# PowerSupplies.net
KiCad netlist of a schematic drawn in Altium Designer
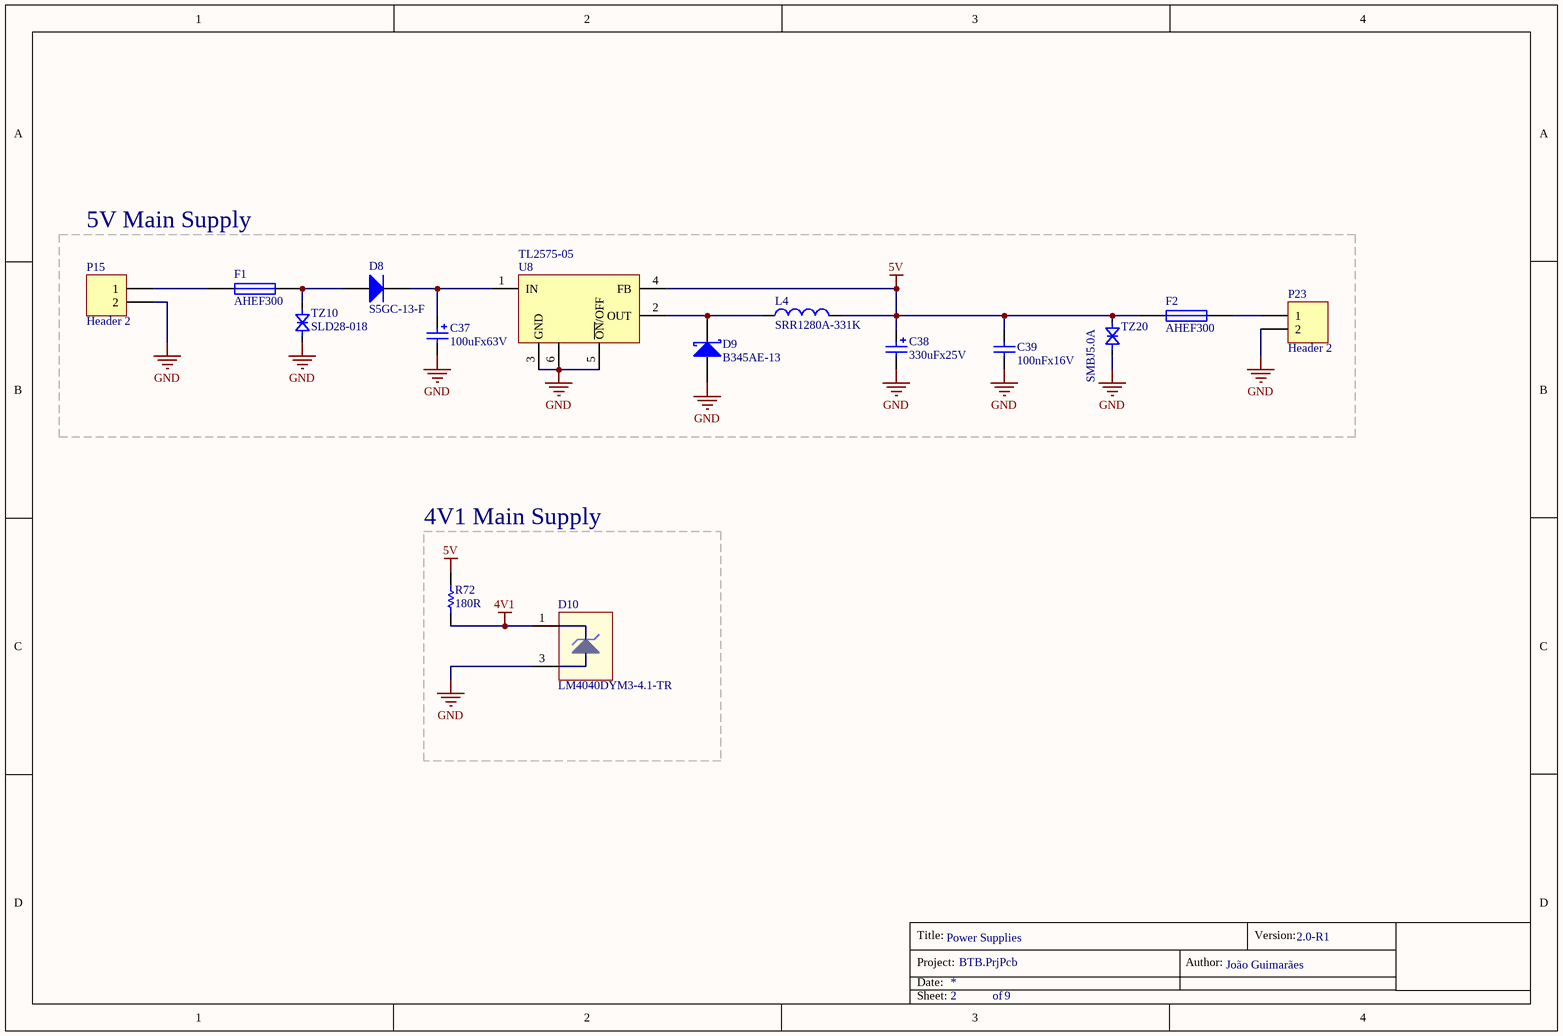
[diagram p0: PowerSupplies.SchDoc]

(export (version "E")
  (design (tool "Eeschema 10.0.6"))
  (components
    (comp (ref "C37")
      (value "100uFx63V")
      (footprint "DISC-CAP-ALU-G")
      (description "Polarized Capacitor (Surface Mount)")
      (libsource (lib "IntLib") (part "Cap Pol"))
    )
    (comp (ref "C38")
      (value "330uFx25V")
      (footprint "DISC-CAP-ALU-F")
      (description "Polarized Capacitor (Surface Mount)")
      (libsource (lib "IntLib") (part "Cap Pol"))
    )
    (comp (ref "C39")
      (value "100nFx16V")
      (footprint "DISC-0805")
      (description "Capacitor")
      (libsource (lib "IntLib") (part "Cap"))
    )
    (comp (ref "D8")
      (value "S5GC-13-F")
      (footprint "DISC-DO214-AB")
      (description "Default Diode")
      (fields (field (name "PUBLISHER") "Altium Limited"))
      (libsource (lib "IntLib") (part "Diode"))
    )
    (comp (ref "D9")
      (value "B345AE-13")
      (footprint "DISC-DO214-AC")
      (description "Schottky Diode")
      (fields (field (name "PUBLISHER") "Altium Limited"))
      (libsource (lib "IntLib") (part "D Schottky"))
    )
    (comp (ref "D10")
      (value "LM4040DYM3-4.1-TR")
      (footprint "DISC-SOT-23")
      (description "Shunt Voltage References")
      (libsource (lib "IntLib") (part "LM4040"))
    )
    (comp (ref "F1")
      (value "AHEF300")
      (footprint "DISC-PTC-0.2X0.4")
      (description "Fuse")
      (fields (field (name "PUBLISHER") "Altium Limited"))
      (libsource (lib "IntLib") (part "Fuse 1"))
    )
    (comp (ref "F2")
      (value "AHEF300")
      (footprint "DISC-PTC-0.2X0.4")
      (description "Fuse")
      (fields (field (name "PUBLISHER") "Altium Limited"))
      (libsource (lib "IntLib") (part "Fuse 1"))
    )
    (comp (ref "L4")
      (value "SRR1280A-331K")
      (footprint "DISC-IND-5050")
      (description "Chip Inductor")
      (libsource (lib "IntLib") (part "Inductor"))
    )
    (comp (ref "P15")
      (value "Header 2")
      (footprint "CON-FLEXWIRE-1.5MM2-1X2")
      (description "Header, 2-Pin")
      (fields (field (name "PUBLISHER") "Altium Limited"))
      (libsource (lib "IntLib") (part "Header 2"))
    )
    (comp (ref "P23")
      (value "Header 2")
      (footprint "CON-FLEXWIRE-1.5MM2-1X2")
      (description "Header, 2-Pin")
      (fields (field (name "PUBLISHER") "Altium Limited"))
      (libsource (lib "") (part "Header 2_1"))
    )
    (comp (ref "R72")
      (value "180R")
      (footprint "DISC-0805")
      (description "Resistor")
      (libsource (lib "IntLib") (part "Res"))
    )
    (comp (ref "TZ10")
      (value "SLD28-018")
      (footprint "DISC-DIODE-0.9-V")
      (description "TVZ-Bi-Directional")
      (libsource (lib "IntLib") (part "TVZ-Bi-Directional"))
    )
    (comp (ref "TZ20")
      (value "SMBJ5.0A")
      (footprint "DISC-DO214-AA")
      (description "TVZ-Bi-Directional")
      (libsource (lib "IntLib") (part "TVZ-Bi-Directional"))
    )
    (comp (ref "U8")
      (value "TL2575-05")
      (footprint "CI-TO-263")
      (description "Switching Voltage Regulators 1-A Step-Down Voltage")
      (libsource (lib "IntLib") (part "TL2575-05IKTTR"))
    )
  )
  (nets
    (net (code "1") (name "4V1") (class "Default")
      (node (ref "D10") (pin "1") (pinfunction "A_1") (pintype "passive"))
      (node (ref "R72") (pin "1") (pinfunction "1_1") (pintype "passive"))
    )
    (net (code "2") (name "5V") (class "Default")
      (node (ref "C38") (pin "1") (pinfunction "1_1") (pintype "passive"))
      (node (ref "C39") (pin "2") (pinfunction "2_2") (pintype "passive"))
      (node (ref "F2") (pin "1") (pinfunction "1_1") (pintype "passive"))
      (node (ref "L4") (pin "2") (pinfunction "2_2") (pintype "passive"))
      (node (ref "R72") (pin "2") (pinfunction "2_2") (pintype "passive"))
      (node (ref "TZ20") (pin "2") (pinfunction "K_2") (pintype "passive"))
      (node (ref "U8") (pin "4") (pinfunction "FB_4") (pintype "passive"))
    )
    (net (code "3") (name "GND") (class "Default")
      (node (ref "C37") (pin "2") (pinfunction "2_2") (pintype "passive"))
      (node (ref "C38") (pin "2") (pinfunction "2_2") (pintype "passive"))
      (node (ref "C39") (pin "1") (pinfunction "1_1") (pintype "passive"))
      (node (ref "D10") (pin "3") (pinfunction "K_3") (pintype "passive"))
      (node (ref "D9") (pin "1") (pinfunction "A_1") (pintype "passive"))
      (node (ref "P15") (pin "2") (pinfunction "2_2") (pintype "passive"))
      (node (ref "P23") (pin "2") (pinfunction "2_2") (pintype "passive"))
      (node (ref "TZ10") (pin "1") (pinfunction "A_1") (pintype "passive"))
      (node (ref "TZ20") (pin "1") (pinfunction "A_1") (pintype "passive"))
      (node (ref "U8") (pin "3") (pinfunction "GND_3") (pintype "power_in"))
      (node (ref "U8") (pin "5") (pinfunction "~{ON}/OFF_5") (pintype "power_in"))
      (node (ref "U8") (pin "6") (pinfunction "GND_6") (pintype "power_in"))
    )
    (net (code "4") (name "Net-(D8-A)") (class "Default")
      (node (ref "D8") (pin "1") (pinfunction "A_1") (pintype "passive"))
      (node (ref "F1") (pin "2") (pinfunction "2_2") (pintype "passive"))
      (node (ref "TZ10") (pin "2") (pinfunction "K_2") (pintype "passive"))
    )
    (net (code "5") (name "Net-(D8-K)") (class "Default")
      (node (ref "C37") (pin "1") (pinfunction "1_1") (pintype "passive"))
      (node (ref "D8") (pin "2") (pinfunction "K_2") (pintype "passive"))
      (node (ref "U8") (pin "1") (pinfunction "IN_1") (pintype "power_in"))
    )
    (net (code "6") (name "Net-(D9-K)") (class "Default")
      (node (ref "D9") (pin "2") (pinfunction "K_2") (pintype "passive"))
      (node (ref "L4") (pin "1") (pinfunction "1_1") (pintype "passive"))
      (node (ref "U8") (pin "2") (pinfunction "OUT_2") (pintype "power_in"))
    )
    (net (code "7") (name "Net-(F1-Pad1)") (class "Default")
      (node (ref "F1") (pin "1") (pinfunction "1_1") (pintype "passive"))
      (node (ref "P15") (pin "1") (pinfunction "1_1") (pintype "passive"))
    )
    (net (code "8") (name "Net-(F2-Pad2)") (class "Default")
      (node (ref "F2") (pin "2") (pinfunction "2_2") (pintype "passive"))
      (node (ref "P23") (pin "1") (pinfunction "1_1") (pintype "passive"))
    )
    (net (code "9") (name "unconnected-(D10-Pad2)") (class "Default")
      (node (ref "D10") (pin "2") (pinfunction "2_2") (pintype "passive"))
    )
  )
)
